# tick-mk-4_6_2.net
KiCad netlist of a schematic drawn in EAGLE
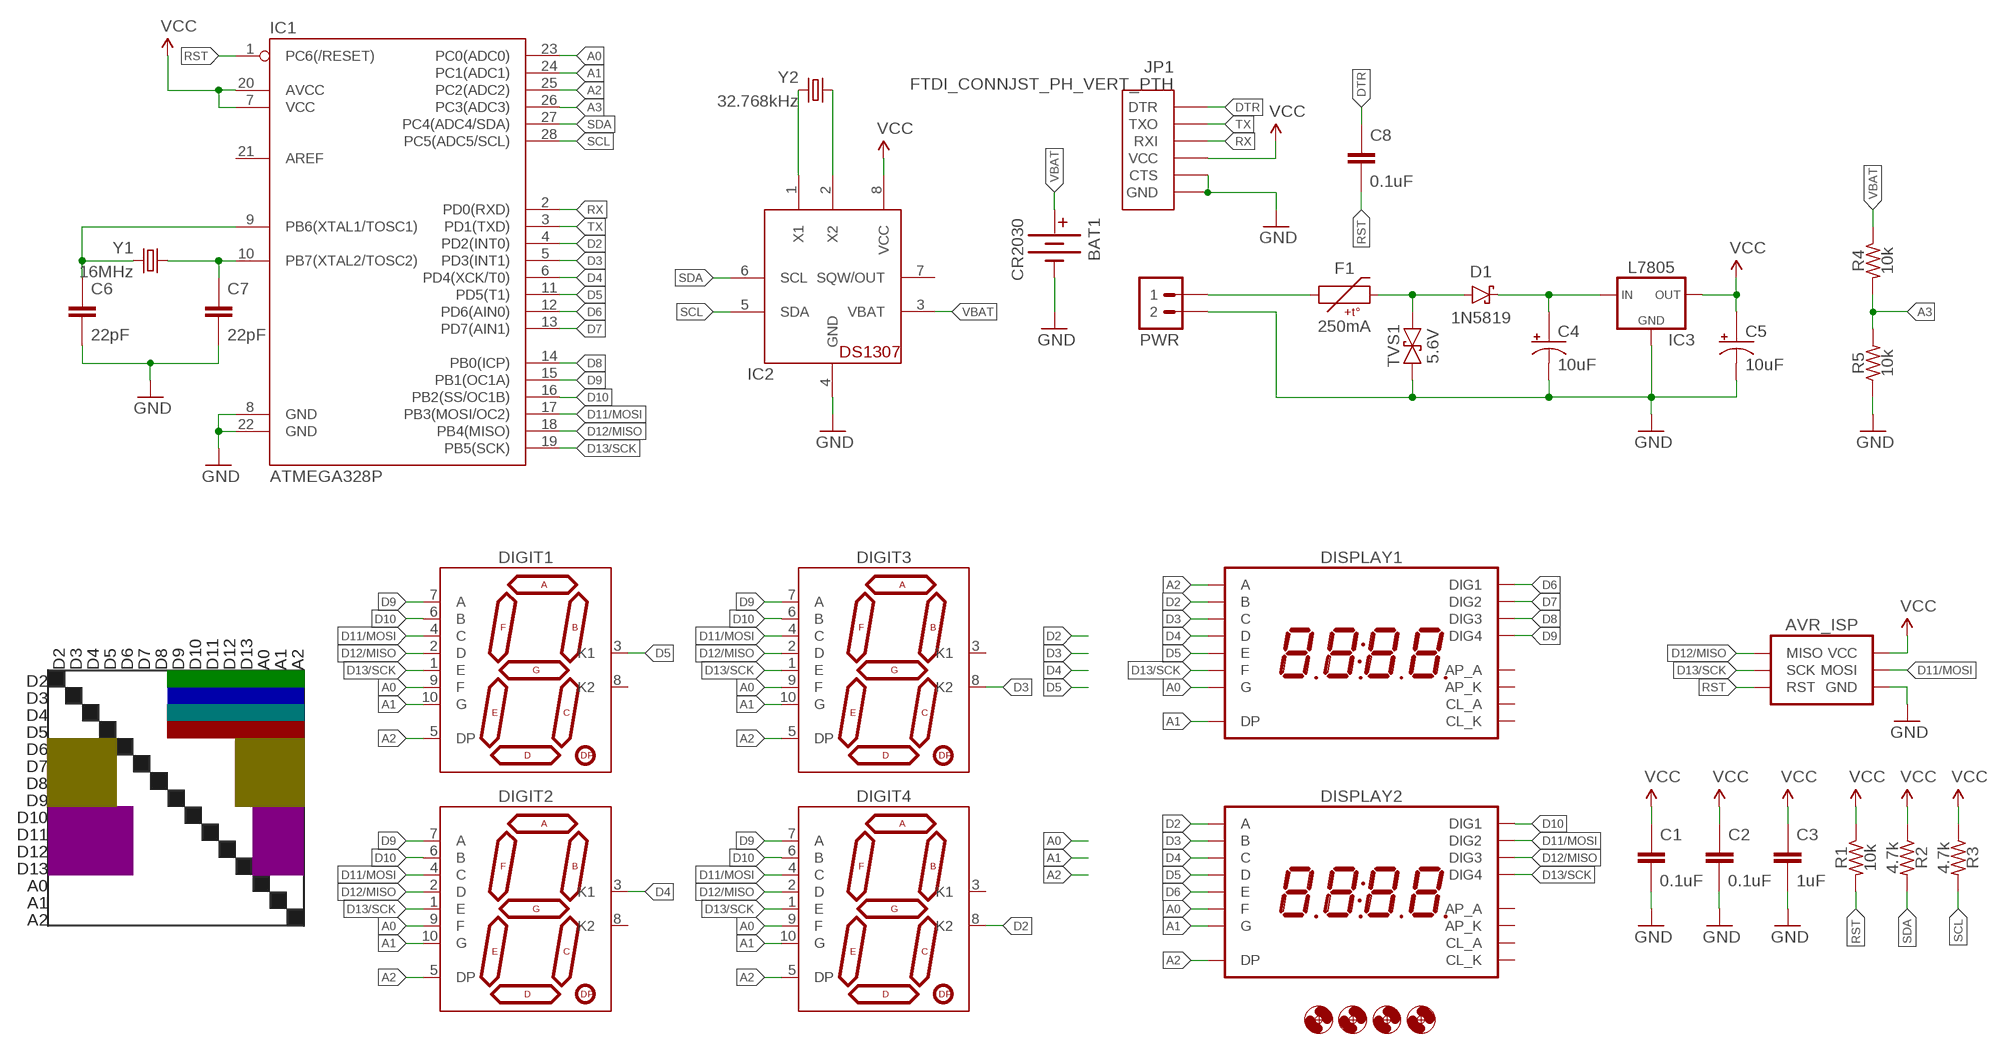
[diagram p0: schematic, sheet 1]

(export (version "E")
  (design (tool "Eeschema 10.0.6"))
  (components
    (comp (ref "AVR_ISP")
      (value "AVR_SPI_PRG_6PTH")
      (footprint "eagle-import:2X3")
      (libsource (lib "eagle-import") (part "AVR_SPI_PRG_6PTH"))
    )
    (comp (ref "BAT1")
      (value "CR2030")
      (footprint "eagle-import:BATTCON_20MM_MINE")
      (libsource (lib "eagle-import") (part "BATTERY20MMSMD-MINE"))
    )
    (comp (ref "C1")
      (value "0.1uF")
      (footprint "eagle-import:C025-024X044")
      (libsource (lib "eagle-import") (part "CAPACITOR-CERAMIC025-024X044"))
    )
    (comp (ref "C2")
      (value "0.1uF")
      (footprint "eagle-import:C025-024X044")
      (libsource (lib "eagle-import") (part "CAPACITOR-CERAMIC025-024X044"))
    )
    (comp (ref "C3")
      (value "1uF")
      (footprint "eagle-import:C025-024X044")
      (libsource (lib "eagle-import") (part "CAPACITOR-CERAMIC025-024X044"))
    )
    (comp (ref "C4")
      (value "10uF")
      (footprint "eagle-import:E2-5")
      (libsource (lib "eagle-import") (part "CAPACITOR-POLARIZEDE2-5"))
    )
    (comp (ref "C5")
      (value "10uF")
      (footprint "eagle-import:E2-5")
      (libsource (lib "eagle-import") (part "CAPACITOR-POLARIZEDE2-5"))
    )
    (comp (ref "C6")
      (value "22pF")
      (footprint "eagle-import:C025-024X044")
      (libsource (lib "eagle-import") (part "CAPACITOR-CERAMIC025-024X044"))
    )
    (comp (ref "C7")
      (value "22pF")
      (footprint "eagle-import:C025-024X044")
      (libsource (lib "eagle-import") (part "CAPACITOR-CERAMIC025-024X044"))
    )
    (comp (ref "C8")
      (value "0.1uF")
      (footprint "eagle-import:C025-024X044")
      (libsource (lib "eagle-import") (part "CAPACITOR-CERAMIC025-024X044"))
    )
    (comp (ref "D1")
      (value "1N5819")
      (footprint "eagle-import:DIODE-10.16MM")
      (libsource (lib "eagle-import") (part "DIODE-SCHOTTKYPTH-10.16MM"))
    )
    (comp (ref "DIGIT1")
      (value "7SEG_1DIGPTH-25.4MM-BARE")
      (footprint "eagle-import:7SEG_1DIG_25.4MM_NOSILK")
      (libsource (lib "eagle-import") (part "7SEG_1DIGPTH-25.4MM-BARE"))
    )
    (comp (ref "DIGIT2")
      (value "7SEG_1DIGPTH-25.4MM-BARE")
      (footprint "eagle-import:7SEG_1DIG_25.4MM_NOSILK")
      (libsource (lib "eagle-import") (part "7SEG_1DIGPTH-25.4MM-BARE"))
    )
    (comp (ref "DIGIT3")
      (value "7SEG_1DIGPTH-25.4MM-BARE")
      (footprint "eagle-import:7SEG_1DIG_25.4MM_NOSILK")
      (libsource (lib "eagle-import") (part "7SEG_1DIGPTH-25.4MM-BARE"))
    )
    (comp (ref "DIGIT4")
      (value "7SEG_1DIGPTH-25.4MM-BARE")
      (footprint "eagle-import:7SEG_1DIG_25.4MM_NOSILK")
      (libsource (lib "eagle-import") (part "7SEG_1DIGPTH-25.4MM-BARE"))
    )
    (comp (ref "DISPLAY1")
      (value "7SEG_4DIGIT_COLON_APOS")
      (footprint "eagle-import:7SEG_4DIG_10MM")
      (libsource (lib "eagle-import") (part "7SEG_4DIGIT_COLON_APOS"))
    )
    (comp (ref "DISPLAY2")
      (value "7SEG_4DIGIT_COLON_APOS")
      (footprint "eagle-import:7SEG_4DIG_10MM")
      (libsource (lib "eagle-import") (part "7SEG_4DIGIT_COLON_APOS"))
    )
    (comp (ref "F1")
      (value "250mA")
      (footprint "eagle-import:PTC-PTH-5.08MM")
      (libsource (lib "eagle-import") (part "PTCPTH-5.08MM"))
    )
    (comp (ref "H1")
      (value "HOLE#2")
      (footprint "eagle-import:HOLE-#2")
      (libsource (lib "eagle-import") (part "HOLE#2"))
    )
    (comp (ref "H2")
      (value "HOLE#2")
      (footprint "eagle-import:HOLE-#2")
      (libsource (lib "eagle-import") (part "HOLE#2"))
    )
    (comp (ref "H3")
      (value "HOLE#2")
      (footprint "eagle-import:HOLE-#2")
      (libsource (lib "eagle-import") (part "HOLE#2"))
    )
    (comp (ref "H4")
      (value "HOLE#2")
      (footprint "eagle-import:HOLE-#2")
      (libsource (lib "eagle-import") (part "HOLE#2"))
    )
    (comp (ref "IC1")
      (value "ATMEGA328P")
      (footprint "eagle-import:DIL28-3")
      (libsource (lib "eagle-import") (part "ATMEGA328P_PDIP"))
    )
    (comp (ref "IC2")
      (value "DS1307")
      (footprint "eagle-import:DIL08")
      (libsource (lib "eagle-import") (part "DS1307"))
    )
    (comp (ref "IC3")
      (value "L7805")
      (footprint "eagle-import:TO220-IGO-THERMPAD")
      (libsource (lib "eagle-import") (part "V_REG_78XXTO-220-THERMPAD"))
    )
    (comp (ref "JP1")
      (value "FTDI_CONNJST_PH_VERT_PTH")
      (footprint "eagle-import:FTDI_CONN_JST_PH_VERT_PTH")
      (libsource (lib "eagle-import") (part "FTDI_CONNJST_PH_VERT_PTH"))
    )
    (comp (ref "PWR")
      (value "M02JST-PTH-VERT")
      (footprint "eagle-import:JST-2-PH-VERT-PTH")
      (libsource (lib "eagle-import") (part "M02JST-PTH-VERT"))
    )
    (comp (ref "R1")
      (value "10k")
      (footprint "eagle-import:RESISTOR-AXIAL-PTH-7.62MM")
      (libsource (lib "eagle-import") (part "RESISTORPTH-AXIAL-7.62MM"))
    )
    (comp (ref "R2")
      (value "4.7k")
      (footprint "eagle-import:RESISTOR-AXIAL-PTH-6.35MM")
      (libsource (lib "eagle-import") (part "RESISTORPTH-AXIAL-6.35MM"))
    )
    (comp (ref "R3")
      (value "4.7k")
      (footprint "eagle-import:RESISTOR-AXIAL-PTH-6.35MM")
      (libsource (lib "eagle-import") (part "RESISTORPTH-AXIAL-6.35MM"))
    )
    (comp (ref "R4")
      (value "10k")
      (footprint "eagle-import:RESISTOR-AXIAL-PTH-6.35MM")
      (libsource (lib "eagle-import") (part "RESISTORPTH-AXIAL-6.35MM"))
    )
    (comp (ref "R5")
      (value "10k")
      (footprint "eagle-import:RESISTOR-AXIAL-PTH-6.35MM")
      (libsource (lib "eagle-import") (part "RESISTORPTH-AXIAL-6.35MM"))
    )
    (comp (ref "TVS1")
      (value "5.6V")
      (footprint "eagle-import:DO-41-TVS-BI-10.16MM")
      (libsource (lib "eagle-import") (part "TVSDO-41-10.16MM"))
    )
    (comp (ref "Y1")
      (value "16MHz")
      (footprint "eagle-import:HC49U-V")
      (libsource (lib "eagle-import") (part "CRYSTALHC49UV"))
    )
    (comp (ref "Y2")
      (value "32.768kHz")
      (footprint "eagle-import:TC26H")
      (libsource (lib "eagle-import") (part "CRYSTALTC26H"))
    )
  )
  (nets
    (net (code "1") (name "A0") (class "Default")
      (node (ref "DIGIT1") (pin "9") (pinfunction "F_9") (pintype "bidirectional"))
      (node (ref "DIGIT2") (pin "9") (pinfunction "F_9") (pintype "bidirectional"))
      (node (ref "DIGIT3") (pin "9") (pinfunction "F_9") (pintype "bidirectional"))
      (node (ref "DIGIT4") (pin "9") (pinfunction "F_9") (pintype "bidirectional"))
      (node (ref "DISPLAY1") (pin "15") (pinfunction "G_15") (pintype "passive"))
      (node (ref "DISPLAY2") (pin "11") (pinfunction "F_11") (pintype "passive"))
      (node (ref "IC1") (pin "23") (pinfunction "PC0(ADC0)_23") (pintype "bidirectional"))
    )
    (net (code "2") (name "A1") (class "Default")
      (node (ref "DIGIT1") (pin "10") (pinfunction "G_10") (pintype "bidirectional"))
      (node (ref "DIGIT2") (pin "10") (pinfunction "G_10") (pintype "bidirectional"))
      (node (ref "DIGIT3") (pin "10") (pinfunction "G_10") (pintype "bidirectional"))
      (node (ref "DIGIT4") (pin "10") (pinfunction "G_10") (pintype "bidirectional"))
      (node (ref "DISPLAY1") (pin "7") (pinfunction "DP_7") (pintype "passive"))
      (node (ref "DISPLAY2") (pin "15") (pinfunction "G_15") (pintype "passive"))
      (node (ref "IC1") (pin "24") (pinfunction "PC1(ADC1)_24") (pintype "bidirectional"))
    )
    (net (code "3") (name "A2") (class "Default")
      (node (ref "DIGIT1") (pin "5") (pinfunction "DP_5") (pintype "bidirectional"))
      (node (ref "DIGIT2") (pin "5") (pinfunction "DP_5") (pintype "bidirectional"))
      (node (ref "DIGIT3") (pin "5") (pinfunction "DP_5") (pintype "bidirectional"))
      (node (ref "DIGIT4") (pin "5") (pinfunction "DP_5") (pintype "bidirectional"))
      (node (ref "DISPLAY1") (pin "14") (pinfunction "A_14") (pintype "passive"))
      (node (ref "DISPLAY2") (pin "7") (pinfunction "DP_7") (pintype "passive"))
      (node (ref "IC1") (pin "25") (pinfunction "PC2(ADC2)_25") (pintype "bidirectional"))
    )
    (net (code "4") (name "A3") (class "Default")
      (node (ref "IC1") (pin "26") (pinfunction "PC3(ADC3)_26") (pintype "bidirectional"))
      (node (ref "R4") (pin "P$2") (pinfunction "2_P$2") (pintype "passive"))
      (node (ref "R5") (pin "P$2") (pinfunction "2_P$2") (pintype "passive"))
    )
    (net (code "5") (name "D2") (class "Default")
      (node (ref "DIGIT4") (pin "8") (pinfunction "K2_8") (pintype "bidirectional"))
      (node (ref "DISPLAY1") (pin "16") (pinfunction "B_16") (pintype "passive"))
      (node (ref "DISPLAY2") (pin "14") (pinfunction "A_14") (pintype "passive"))
      (node (ref "IC1") (pin "4") (pinfunction "PD2(INT0)_4") (pintype "bidirectional"))
    )
    (net (code "6") (name "D3") (class "Default")
      (node (ref "DIGIT3") (pin "8") (pinfunction "K2_8") (pintype "bidirectional"))
      (node (ref "DISPLAY1") (pin "13") (pinfunction "C_13") (pintype "passive"))
      (node (ref "DISPLAY2") (pin "16") (pinfunction "B_16") (pintype "passive"))
      (node (ref "IC1") (pin "5") (pinfunction "PD3(INT1)_5") (pintype "bidirectional"))
    )
    (net (code "7") (name "D4") (class "Default")
      (node (ref "DIGIT2") (pin "3") (pinfunction "K1_3") (pintype "bidirectional"))
      (node (ref "DISPLAY1") (pin "3") (pinfunction "D_3") (pintype "passive"))
      (node (ref "DISPLAY2") (pin "13") (pinfunction "C_13") (pintype "passive"))
      (node (ref "IC1") (pin "6") (pinfunction "PD4(XCK/T0)_6") (pintype "bidirectional"))
    )
    (net (code "8") (name "D5") (class "Default")
      (node (ref "DIGIT1") (pin "3") (pinfunction "K1_3") (pintype "bidirectional"))
      (node (ref "DISPLAY1") (pin "5") (pinfunction "E_5") (pintype "passive"))
      (node (ref "DISPLAY2") (pin "3") (pinfunction "D_3") (pintype "passive"))
      (node (ref "IC1") (pin "11") (pinfunction "PD5(T1)_11") (pintype "bidirectional"))
    )
    (net (code "9") (name "D6") (class "Default")
      (node (ref "DISPLAY1") (pin "1") (pinfunction "DIG1_1") (pintype "passive"))
      (node (ref "DISPLAY2") (pin "5") (pinfunction "E_5") (pintype "passive"))
      (node (ref "IC1") (pin "12") (pinfunction "PD6(AIN0)_12") (pintype "bidirectional"))
    )
    (net (code "10") (name "D7") (class "Default")
      (node (ref "DISPLAY1") (pin "2") (pinfunction "DIG2_2") (pintype "passive"))
      (node (ref "IC1") (pin "13") (pinfunction "PD7(AIN1)_13") (pintype "bidirectional"))
    )
    (net (code "11") (name "D8") (class "Default")
      (node (ref "DISPLAY1") (pin "6") (pinfunction "DIG3_6") (pintype "passive"))
      (node (ref "IC1") (pin "14") (pinfunction "PB0(ICP)_14") (pintype "bidirectional"))
    )
    (net (code "12") (name "D9") (class "Default")
      (node (ref "DIGIT1") (pin "7") (pinfunction "A_7") (pintype "bidirectional"))
      (node (ref "DIGIT2") (pin "7") (pinfunction "A_7") (pintype "bidirectional"))
      (node (ref "DIGIT3") (pin "7") (pinfunction "A_7") (pintype "bidirectional"))
      (node (ref "DIGIT4") (pin "7") (pinfunction "A_7") (pintype "bidirectional"))
      (node (ref "DISPLAY1") (pin "8") (pinfunction "DIG4_8") (pintype "passive"))
      (node (ref "IC1") (pin "15") (pinfunction "PB1(OC1A)_15") (pintype "bidirectional"))
    )
    (net (code "13") (name "D10") (class "Default")
      (node (ref "DIGIT1") (pin "6") (pinfunction "B_6") (pintype "bidirectional"))
      (node (ref "DIGIT2") (pin "6") (pinfunction "B_6") (pintype "bidirectional"))
      (node (ref "DIGIT3") (pin "6") (pinfunction "B_6") (pintype "bidirectional"))
      (node (ref "DIGIT4") (pin "6") (pinfunction "B_6") (pintype "bidirectional"))
      (node (ref "DISPLAY2") (pin "1") (pinfunction "DIG1_1") (pintype "passive"))
      (node (ref "IC1") (pin "16") (pinfunction "PB2(SS/OC1B)_16") (pintype "bidirectional"))
    )
    (net (code "14") (name "D11{slash}MOSI") (class "Default")
      (node (ref "AVR_ISP") (pin "4") (pinfunction "MOSI_4") (pintype "passive"))
      (node (ref "DIGIT1") (pin "4") (pinfunction "C_4") (pintype "bidirectional"))
      (node (ref "DIGIT2") (pin "4") (pinfunction "C_4") (pintype "bidirectional"))
      (node (ref "DIGIT3") (pin "4") (pinfunction "C_4") (pintype "bidirectional"))
      (node (ref "DIGIT4") (pin "4") (pinfunction "C_4") (pintype "bidirectional"))
      (node (ref "DISPLAY2") (pin "2") (pinfunction "DIG2_2") (pintype "passive"))
      (node (ref "IC1") (pin "17") (pinfunction "PB3(MOSI/OC2)_17") (pintype "bidirectional"))
    )
    (net (code "15") (name "D12{slash}MISO") (class "Default")
      (node (ref "AVR_ISP") (pin "1") (pinfunction "MISO_1") (pintype "passive"))
      (node (ref "DIGIT1") (pin "2") (pinfunction "D_2") (pintype "bidirectional"))
      (node (ref "DIGIT2") (pin "2") (pinfunction "D_2") (pintype "bidirectional"))
      (node (ref "DIGIT3") (pin "2") (pinfunction "D_2") (pintype "bidirectional"))
      (node (ref "DIGIT4") (pin "2") (pinfunction "D_2") (pintype "bidirectional"))
      (node (ref "DISPLAY2") (pin "6") (pinfunction "DIG3_6") (pintype "passive"))
      (node (ref "IC1") (pin "18") (pinfunction "PB4(MISO)_18") (pintype "bidirectional"))
    )
    (net (code "16") (name "D13{slash}SCK") (class "Default")
      (node (ref "AVR_ISP") (pin "3") (pinfunction "SCK_3") (pintype "passive"))
      (node (ref "DIGIT1") (pin "1") (pinfunction "E_1") (pintype "bidirectional"))
      (node (ref "DIGIT2") (pin "1") (pinfunction "E_1") (pintype "bidirectional"))
      (node (ref "DIGIT3") (pin "1") (pinfunction "E_1") (pintype "bidirectional"))
      (node (ref "DIGIT4") (pin "1") (pinfunction "E_1") (pintype "bidirectional"))
      (node (ref "DISPLAY1") (pin "11") (pinfunction "F_11") (pintype "passive"))
      (node (ref "DISPLAY2") (pin "8") (pinfunction "DIG4_8") (pintype "passive"))
      (node (ref "IC1") (pin "19") (pinfunction "PB5(SCK)_19") (pintype "bidirectional"))
    )
    (net (code "17") (name "DTR") (class "Default")
      (node (ref "C8") (pin "1") (pinfunction "1_1") (pintype "passive"))
      (node (ref "JP1") (pin "DTR") (pinfunction "DTR_DTR") (pintype "bidirectional"))
    )
    (net (code "18") (name "GND") (class "Default")
      (node (ref "AVR_ISP") (pin "6") (pinfunction "GND_6") (pintype "passive"))
      (node (ref "BAT1") (pin "BOTTOM") (pinfunction "-_BOTTOM") (pintype "power_in"))
      (node (ref "C1") (pin "2") (pinfunction "2_2") (pintype "passive"))
      (node (ref "C2") (pin "2") (pinfunction "2_2") (pintype "passive"))
      (node (ref "C3") (pin "2") (pinfunction "2_2") (pintype "passive"))
      (node (ref "C4") (pin "-") (pinfunction "-_-") (pintype "passive"))
      (node (ref "C5") (pin "-") (pinfunction "-_-") (pintype "passive"))
      (node (ref "C6") (pin "2") (pinfunction "2_2") (pintype "passive"))
      (node (ref "C7") (pin "2") (pinfunction "2_2") (pintype "passive"))
      (node (ref "IC1") (pin "22") (pinfunction "GND_22") (pintype "bidirectional"))
      (node (ref "IC1") (pin "8") (pinfunction "GND_8") (pintype "bidirectional"))
      (node (ref "IC2") (pin "4") (pinfunction "GND_4") (pintype "power_in"))
      (node (ref "IC3") (pin "4") (pinfunction "GND_4") (pintype "bidirectional"))
      (node (ref "IC3") (pin "GND") (pinfunction "GND_GND") (pintype "bidirectional"))
      (node (ref "JP1") (pin "CTS") (pinfunction "CTS_CTS") (pintype "bidirectional"))
      (node (ref "JP1") (pin "GND") (pinfunction "GND_GND") (pintype "bidirectional"))
      (node (ref "PWR") (pin "2") (pinfunction "2_2") (pintype "passive"))
      (node (ref "R5") (pin "P$1") (pinfunction "1_P$1") (pintype "passive"))
      (node (ref "TVS1") (pin "P$1") (pinfunction "1_P$1") (pintype "passive"))
    )
    (net (code "19") (name "Net-(C4-Pad+)") (class "Default")
      (node (ref "C4") (pin "+") (pinfunction "+_+") (pintype "passive"))
      (node (ref "D1") (pin "C") (pinfunction "C_C") (pintype "passive"))
      (node (ref "IC3") (pin "IN") (pinfunction "IN_IN") (pintype "bidirectional"))
    )
    (net (code "20") (name "Net-(F1-1)") (class "Default")
      (node (ref "F1") (pin "P$1") (pinfunction "1_P$1") (pintype "passive"))
      (node (ref "PWR") (pin "1") (pinfunction "1_1") (pintype "passive"))
    )
    (net (code "21") (name "Net-(F1-2)") (class "Default")
      (node (ref "D1") (pin "A") (pinfunction "A_A") (pintype "passive"))
      (node (ref "F1") (pin "P$2") (pinfunction "2_P$2") (pintype "passive"))
      (node (ref "TVS1") (pin "P$2") (pinfunction "2_P$2") (pintype "passive"))
    )
    (net (code "22") (name "Net-(IC1-PB6(XTAL1{slash}TOSC1))") (class "Default")
      (node (ref "C6") (pin "1") (pinfunction "1_1") (pintype "passive"))
      (node (ref "IC1") (pin "9") (pinfunction "PB6(XTAL1/TOSC1)_9") (pintype "bidirectional"))
      (node (ref "Y1") (pin "2") (pinfunction "2_2") (pintype "passive"))
    )
    (net (code "23") (name "Net-(IC1-PB7(XTAL2{slash}TOSC2))") (class "Default")
      (node (ref "C7") (pin "1") (pinfunction "1_1") (pintype "passive"))
      (node (ref "IC1") (pin "10") (pinfunction "PB7(XTAL2/TOSC2)_10") (pintype "bidirectional"))
      (node (ref "Y1") (pin "1") (pinfunction "1_1") (pintype "passive"))
    )
    (net (code "24") (name "Net-(IC2-X1)") (class "Default")
      (node (ref "IC2") (pin "1") (pinfunction "X1_1") (pintype "passive"))
      (node (ref "Y2") (pin "2") (pinfunction "2_2") (pintype "passive"))
    )
    (net (code "25") (name "Net-(IC2-X2)") (class "Default")
      (node (ref "IC2") (pin "2") (pinfunction "X2_2") (pintype "passive"))
      (node (ref "Y2") (pin "1") (pinfunction "1_1") (pintype "passive"))
    )
    (net (code "26") (name "RST") (class "Default")
      (node (ref "AVR_ISP") (pin "5") (pinfunction "RST_5") (pintype "passive"))
      (node (ref "C8") (pin "2") (pinfunction "2_2") (pintype "passive"))
      (node (ref "IC1") (pin "1") (pinfunction "PC6(/RESET)_1") (pintype "bidirectional"))
      (node (ref "R1") (pin "P$2") (pinfunction "2_P$2") (pintype "passive"))
    )
    (net (code "27") (name "RX") (class "Default")
      (node (ref "IC1") (pin "2") (pinfunction "PD0(RXD)_2") (pintype "bidirectional"))
      (node (ref "JP1") (pin "RXI") (pinfunction "RXI_RXI") (pintype "bidirectional"))
    )
    (net (code "28") (name "SCL") (class "Default")
      (node (ref "IC1") (pin "28") (pinfunction "PC5(ADC5/SCL)_28") (pintype "bidirectional"))
      (node (ref "IC2") (pin "5") (pinfunction "SDA_5") (pintype "bidirectional"))
      (node (ref "R3") (pin "P$2") (pinfunction "2_P$2") (pintype "passive"))
    )
    (net (code "29") (name "SDA") (class "Default")
      (node (ref "IC1") (pin "27") (pinfunction "PC4(ADC4/SDA)_27") (pintype "bidirectional"))
      (node (ref "IC2") (pin "6") (pinfunction "SCL_6") (pintype "bidirectional"))
      (node (ref "R2") (pin "P$2") (pinfunction "2_P$2") (pintype "passive"))
    )
    (net (code "30") (name "TX") (class "Default")
      (node (ref "IC1") (pin "3") (pinfunction "PD1(TXD)_3") (pintype "bidirectional"))
      (node (ref "JP1") (pin "TXO") (pinfunction "TXO_TXO") (pintype "bidirectional"))
    )
    (net (code "31") (name "VBAT") (class "Default")
      (node (ref "BAT1") (pin "TOP@1") (pinfunction "+_TOP@1") (pintype "power_in"))
      (node (ref "BAT1") (pin "TOP@2") (pinfunction "+_TOP@2") (pintype "power_in"))
      (node (ref "IC2") (pin "3") (pinfunction "VBAT_3") (pintype "power_in"))
      (node (ref "R4") (pin "P$1") (pinfunction "1_P$1") (pintype "passive"))
    )
    (net (code "32") (name "VCC") (class "Default")
      (node (ref "AVR_ISP") (pin "2") (pinfunction "VCC_2") (pintype "passive"))
      (node (ref "C1") (pin "1") (pinfunction "1_1") (pintype "passive"))
      (node (ref "C2") (pin "1") (pinfunction "1_1") (pintype "passive"))
      (node (ref "C3") (pin "1") (pinfunction "1_1") (pintype "passive"))
      (node (ref "C5") (pin "+") (pinfunction "+_+") (pintype "passive"))
      (node (ref "IC1") (pin "20") (pinfunction "AVCC_20") (pintype "bidirectional"))
      (node (ref "IC1") (pin "7") (pinfunction "VCC_7") (pintype "bidirectional"))
      (node (ref "IC2") (pin "8") (pinfunction "VCC_8") (pintype "power_in"))
      (node (ref "IC3") (pin "OUT") (pinfunction "OUT_OUT") (pintype "bidirectional"))
      (node (ref "JP1") (pin "VCC") (pinfunction "VCC_VCC") (pintype "bidirectional"))
      (node (ref "R1") (pin "P$1") (pinfunction "1_P$1") (pintype "passive"))
      (node (ref "R2") (pin "P$1") (pinfunction "1_P$1") (pintype "passive"))
      (node (ref "R3") (pin "P$1") (pinfunction "1_P$1") (pintype "passive"))
    )
    (net (code "33") (name "unconnected-(DIGIT1-K2-Pad8)") (class "Default")
      (node (ref "DIGIT1") (pin "8") (pinfunction "K2_8") (pintype "bidirectional"))
    )
    (net (code "34") (name "unconnected-(DIGIT2-K2-Pad8)") (class "Default")
      (node (ref "DIGIT2") (pin "8") (pinfunction "K2_8") (pintype "bidirectional"))
    )
    (net (code "35") (name "unconnected-(DIGIT3-K1-Pad3)") (class "Default")
      (node (ref "DIGIT3") (pin "3") (pinfunction "K1_3") (pintype "bidirectional"))
    )
    (net (code "36") (name "unconnected-(DIGIT4-K1-Pad3)") (class "Default")
      (node (ref "DIGIT4") (pin "3") (pinfunction "K1_3") (pintype "bidirectional"))
    )
    (net (code "37") (name "unconnected-(DISPLAY1-AP_A-Pad10)") (class "Default")
      (node (ref "DISPLAY1") (pin "10") (pinfunction "AP_A_10") (pintype "bidirectional"))
    )
    (net (code "38") (name "unconnected-(DISPLAY1-AP_K-Pad9)") (class "Default")
      (node (ref "DISPLAY1") (pin "9") (pinfunction "AP_K_9") (pintype "bidirectional"))
    )
    (net (code "39") (name "unconnected-(DISPLAY1-CL_A-Pad4)") (class "Default")
      (node (ref "DISPLAY1") (pin "4") (pinfunction "CL_A_4") (pintype "passive"))
    )
    (net (code "40") (name "unconnected-(DISPLAY1-CL_K-Pad12)") (class "Default")
      (node (ref "DISPLAY1") (pin "12") (pinfunction "CL_K_12") (pintype "passive"))
    )
    (net (code "41") (name "unconnected-(DISPLAY2-AP_A-Pad10)") (class "Default")
      (node (ref "DISPLAY2") (pin "10") (pinfunction "AP_A_10") (pintype "bidirectional"))
    )
    (net (code "42") (name "unconnected-(DISPLAY2-AP_K-Pad9)") (class "Default")
      (node (ref "DISPLAY2") (pin "9") (pinfunction "AP_K_9") (pintype "bidirectional"))
    )
    (net (code "43") (name "unconnected-(DISPLAY2-CL_A-Pad4)") (class "Default")
      (node (ref "DISPLAY2") (pin "4") (pinfunction "CL_A_4") (pintype "passive"))
    )
    (net (code "44") (name "unconnected-(DISPLAY2-CL_K-Pad12)") (class "Default")
      (node (ref "DISPLAY2") (pin "12") (pinfunction "CL_K_12") (pintype "passive"))
    )
    (net (code "45") (name "unconnected-(IC1-AREF-Pad21)") (class "Default")
      (node (ref "IC1") (pin "21") (pinfunction "AREF_21") (pintype "bidirectional"))
    )
    (net (code "46") (name "unconnected-(IC2-SQW{slash}OUT-Pad7)") (class "Default")
      (node (ref "IC2") (pin "7") (pinfunction "SQW/OUT_7") (pintype "bidirectional"))
    )
  )
)
